# ZB-RC-8_Remote-v01-001.net
KiCad netlist of a schematic drawn in EAGLE
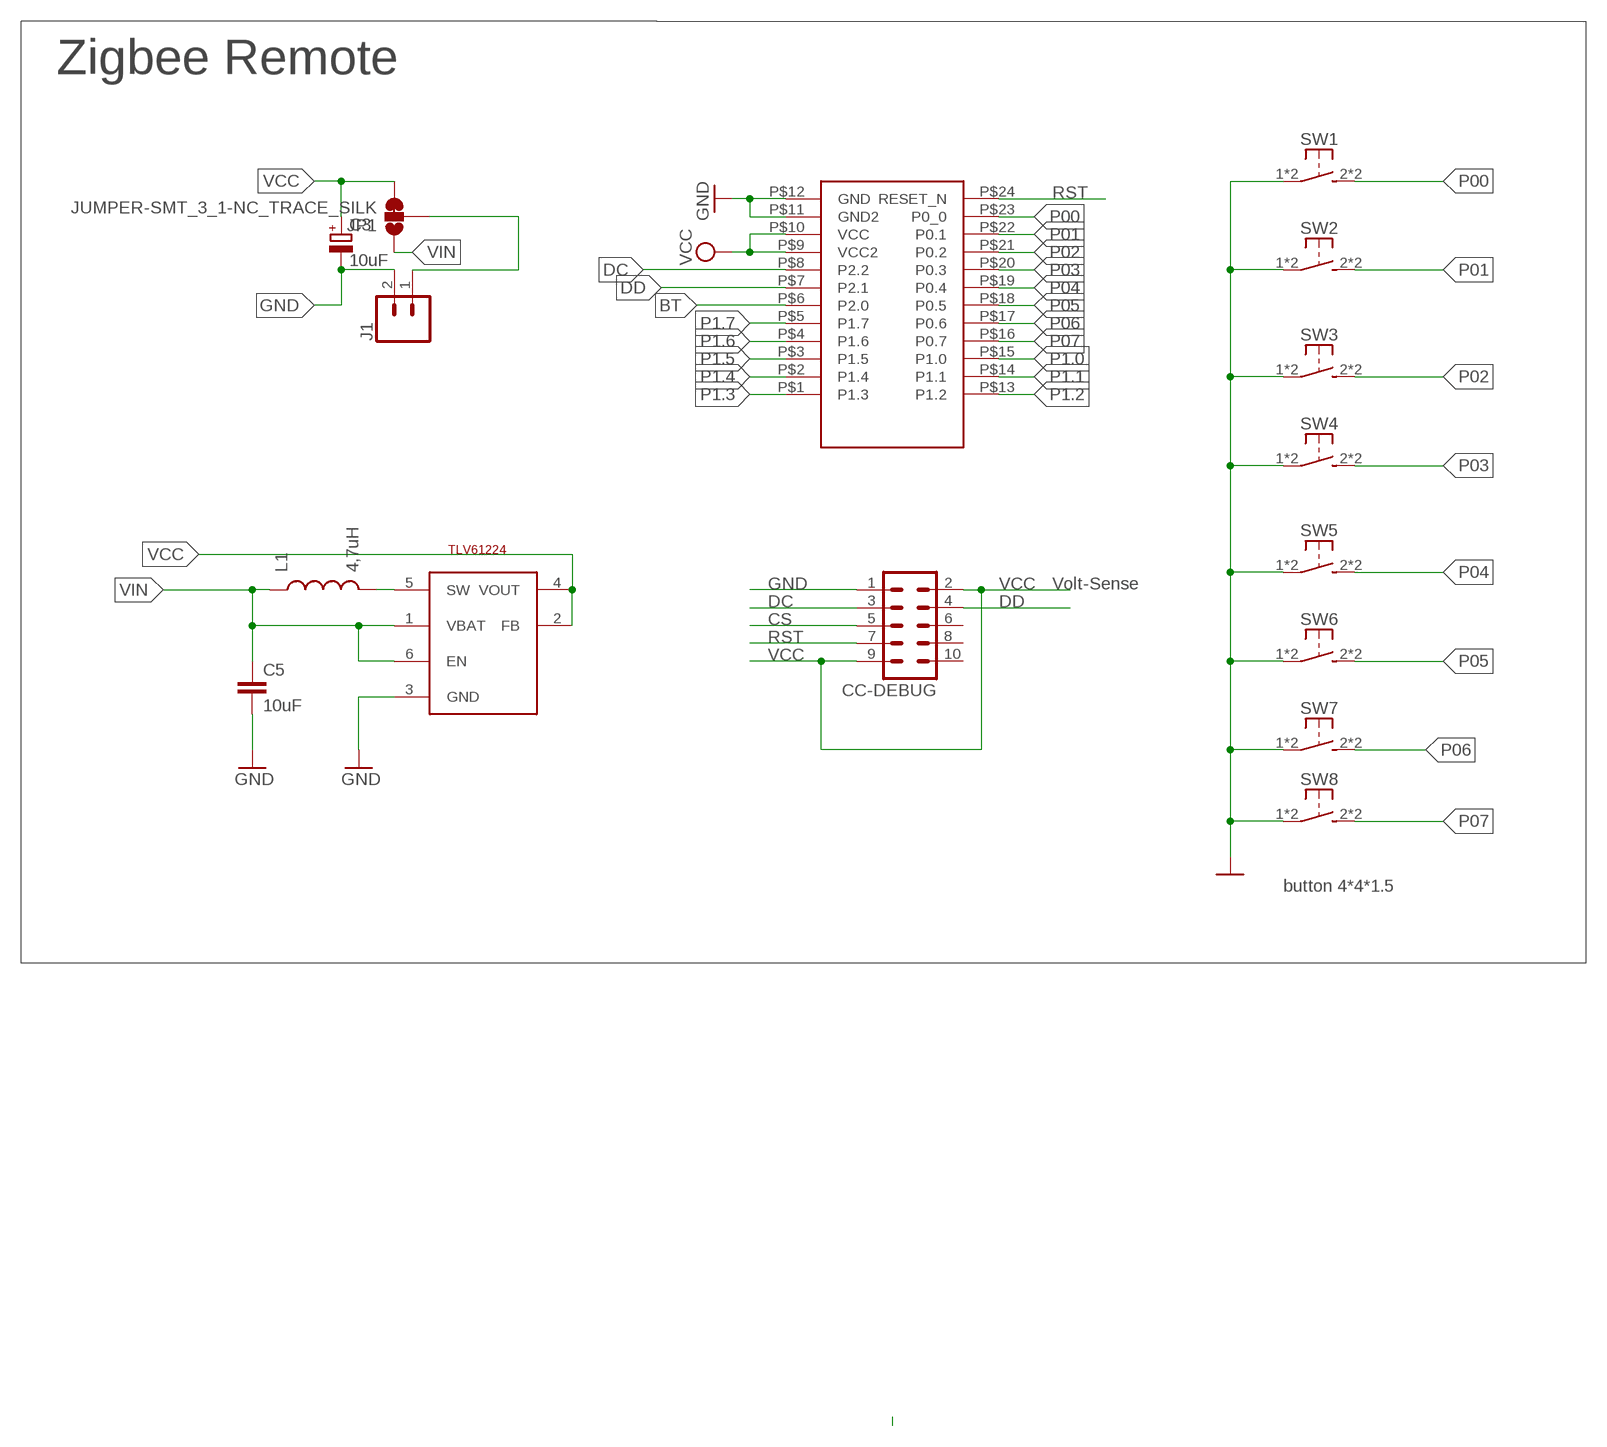
[diagram p0: schematic, sheet 1]

(export (version "E")
  (design (tool "Eeschema 10.0.6"))
  (components
    (comp (ref "C3")
      (value "10uF")
      (footprint "eagle-import:SMC_C")
      (libsource (lib "eagle-import") (part "CPOL-EUSMCC"))
    )
    (comp (ref "C5")
      (value "10uF")
      (footprint "eagle-import:0805")
      (libsource (lib "eagle-import") (part "CAP0805"))
    )
    (comp (ref "CC-DEBUG")
      (value "MA05-2")
      (footprint "eagle-import:MA05-2")
      (libsource (lib "eagle-import") (part "MA05-2"))
    )
    (comp (ref "J1")
      (value "CONN_02PTH3")
      (footprint "eagle-import:1X02_LONGPADS")
      (libsource (lib "eagle-import") (part "CONN_02PTH3"))
    )
    (comp (ref "JP1")
      (value "JUMPER-SMT_3_1-NC_TRACE_SILK")
      (footprint "eagle-import:SMT-JUMPER_3_1-NC_TRACE_SILK")
      (libsource (lib "eagle-import") (part "JUMPER-SMT_3_1-NC_TRACE_SILK"))
    )
    (comp (ref "L1")
      (value "4,7uH")
      (footprint "eagle-import:0805")
      (libsource (lib "eagle-import") (part "INDUCTOR0805"))
    )
    (comp (ref "STEPUP")
      (value "TLV61224")
      (footprint "eagle-import:SOT23-6L")
      (libsource (lib "eagle-import") (part "TI-TLV61224"))
    )
    (comp (ref "SW1")
      (value "SW-TACTILE-TL3305")
      (footprint "eagle-import:TL3305")
      (libsource (lib "eagle-import") (part "SW-TACTILE-TL3305"))
    )
    (comp (ref "SW2")
      (value "SW-TACTILE-TL3305")
      (footprint "eagle-import:TL3305")
      (libsource (lib "eagle-import") (part "SW-TACTILE-TL3305"))
    )
    (comp (ref "SW3")
      (value "SW-TACTILE-TL3305")
      (footprint "eagle-import:TL3305")
      (libsource (lib "eagle-import") (part "SW-TACTILE-TL3305"))
    )
    (comp (ref "SW4")
      (value "SW-TACTILE-TL3305")
      (footprint "eagle-import:TL3305")
      (libsource (lib "eagle-import") (part "SW-TACTILE-TL3305"))
    )
    (comp (ref "SW5")
      (value "SW-TACTILE-TL3305")
      (footprint "eagle-import:TL3305")
      (libsource (lib "eagle-import") (part "SW-TACTILE-TL3305"))
    )
    (comp (ref "SW6")
      (value "SW-TACTILE-TL3305")
      (footprint "eagle-import:TL3305")
      (libsource (lib "eagle-import") (part "SW-TACTILE-TL3305"))
    )
    (comp (ref "SW7")
      (value "SW-TACTILE-TL3305")
      (footprint "eagle-import:TL3305")
      (libsource (lib "eagle-import") (part "SW-TACTILE-TL3305"))
    )
    (comp (ref "SW8")
      (value "SW-TACTILE-TL3305")
      (footprint "eagle-import:TL3305")
      (libsource (lib "eagle-import") (part "SW-TACTILE-TL3305"))
    )
    (comp (ref "U$1")
      (value "CC2530")
      (footprint "eagle-import:SZ1ZIGBEE-SMD")
      (libsource (lib "eagle-import") (part "CC2530"))
    )
  )
  (nets
    (net (code "1") (name "/CS") (class "Default")
      (node (ref "CC-DEBUG") (pin "5") (pinfunction "5_5") (pintype "passive"))
    )
    (net (code "2") (name "/RST") (class "Default")
      (node (ref "CC-DEBUG") (pin "7") (pinfunction "7_7") (pintype "passive"))
      (node (ref "U$1") (pin "P$24") (pinfunction "RESET_N_P$24") (pintype "bidirectional"))
    )
    (net (code "3") (name "BT") (class "Default")
      (node (ref "U$1") (pin "P$6") (pinfunction "P2.0_P$6") (pintype "bidirectional"))
    )
    (net (code "4") (name "DC") (class "Default")
      (node (ref "CC-DEBUG") (pin "3") (pinfunction "3_3") (pintype "passive"))
      (node (ref "U$1") (pin "P$8") (pinfunction "P2.2_P$8") (pintype "bidirectional"))
    )
    (net (code "5") (name "DD") (class "Default")
      (node (ref "CC-DEBUG") (pin "4") (pinfunction "4_4") (pintype "passive"))
      (node (ref "U$1") (pin "P$7") (pinfunction "P2.1_P$7") (pintype "bidirectional"))
    )
    (net (code "6") (name "GND") (class "Default")
      (node (ref "C3") (pin "-") (pinfunction "-_-") (pintype "passive"))
      (node (ref "C5") (pin "2") (pinfunction "2_2") (pintype "passive"))
      (node (ref "CC-DEBUG") (pin "1") (pinfunction "1_1") (pintype "passive"))
      (node (ref "J1") (pin "2") (pinfunction "2_2") (pintype "passive"))
      (node (ref "STEPUP") (pin "3") (pinfunction "GND_3") (pintype "power_in"))
      (node (ref "SW1") (pin "1") (pinfunction "P1_1") (pintype "passive"))
      (node (ref "SW1") (pin "4") (pinfunction "P1_4") (pintype "passive"))
      (node (ref "SW2") (pin "1") (pinfunction "P1_1") (pintype "passive"))
      (node (ref "SW2") (pin "4") (pinfunction "P1_4") (pintype "passive"))
      (node (ref "SW3") (pin "1") (pinfunction "P1_1") (pintype "passive"))
      (node (ref "SW3") (pin "4") (pinfunction "P1_4") (pintype "passive"))
      (node (ref "SW4") (pin "1") (pinfunction "P1_1") (pintype "passive"))
      (node (ref "SW4") (pin "4") (pinfunction "P1_4") (pintype "passive"))
      (node (ref "SW5") (pin "1") (pinfunction "P1_1") (pintype "passive"))
      (node (ref "SW5") (pin "4") (pinfunction "P1_4") (pintype "passive"))
      (node (ref "SW6") (pin "1") (pinfunction "P1_1") (pintype "passive"))
      (node (ref "SW6") (pin "4") (pinfunction "P1_4") (pintype "passive"))
      (node (ref "SW7") (pin "1") (pinfunction "P1_1") (pintype "passive"))
      (node (ref "SW7") (pin "4") (pinfunction "P1_4") (pintype "passive"))
      (node (ref "SW8") (pin "1") (pinfunction "P1_1") (pintype "passive"))
      (node (ref "SW8") (pin "4") (pinfunction "P1_4") (pintype "passive"))
      (node (ref "U$1") (pin "P$11") (pinfunction "GND2_P$11") (pintype "bidirectional"))
      (node (ref "U$1") (pin "P$12") (pinfunction "GND_P$12") (pintype "bidirectional"))
    )
    (net (code "7") (name "Net-(J1-Pad1)") (class "Default")
      (node (ref "J1") (pin "1") (pinfunction "1_1") (pintype "passive"))
      (node (ref "JP1") (pin "2") (pinfunction "2_2") (pintype "passive"))
    )
    (net (code "8") (name "Net-(STEPUP-SW)") (class "Default")
      (node (ref "L1") (pin "2") (pinfunction "2_2") (pintype "passive"))
      (node (ref "STEPUP") (pin "5") (pinfunction "SW_5") (pintype "power_in"))
    )
    (net (code "9") (name "P00") (class "Default")
      (node (ref "SW1") (pin "2") (pinfunction "S1_2") (pintype "passive"))
      (node (ref "SW1") (pin "3") (pinfunction "S1_3") (pintype "passive"))
      (node (ref "U$1") (pin "P$23") (pinfunction "P0_0_P$23") (pintype "bidirectional"))
    )
    (net (code "10") (name "P01") (class "Default")
      (node (ref "SW2") (pin "2") (pinfunction "S1_2") (pintype "passive"))
      (node (ref "SW2") (pin "3") (pinfunction "S1_3") (pintype "passive"))
      (node (ref "U$1") (pin "P$22") (pinfunction "P0.1_P$22") (pintype "bidirectional"))
    )
    (net (code "11") (name "P1.0") (class "Default")
      (node (ref "U$1") (pin "P$15") (pinfunction "P1.0_P$15") (pintype "bidirectional"))
    )
    (net (code "12") (name "P1.1") (class "Default")
      (node (ref "U$1") (pin "P$14") (pinfunction "P1.1_P$14") (pintype "bidirectional"))
    )
    (net (code "13") (name "P1.2") (class "Default")
      (node (ref "U$1") (pin "P$13") (pinfunction "P1.2_P$13") (pintype "bidirectional"))
    )
    (net (code "14") (name "P1.3") (class "Default")
      (node (ref "U$1") (pin "P$1") (pinfunction "P1.3_P$1") (pintype "bidirectional"))
    )
    (net (code "15") (name "P1.4") (class "Default")
      (node (ref "U$1") (pin "P$2") (pinfunction "P1.4_P$2") (pintype "bidirectional"))
    )
    (net (code "16") (name "P1.5") (class "Default")
      (node (ref "U$1") (pin "P$3") (pinfunction "P1.5_P$3") (pintype "bidirectional"))
    )
    (net (code "17") (name "P1.6") (class "Default")
      (node (ref "U$1") (pin "P$4") (pinfunction "P1.6_P$4") (pintype "bidirectional"))
    )
    (net (code "18") (name "P1.7") (class "Default")
      (node (ref "U$1") (pin "P$5") (pinfunction "P1.7_P$5") (pintype "bidirectional"))
    )
    (net (code "19") (name "P02") (class "Default")
      (node (ref "SW3") (pin "2") (pinfunction "S1_2") (pintype "passive"))
      (node (ref "SW3") (pin "3") (pinfunction "S1_3") (pintype "passive"))
      (node (ref "U$1") (pin "P$21") (pinfunction "P0.2_P$21") (pintype "bidirectional"))
    )
    (net (code "20") (name "P03") (class "Default")
      (node (ref "SW4") (pin "2") (pinfunction "S1_2") (pintype "passive"))
      (node (ref "SW4") (pin "3") (pinfunction "S1_3") (pintype "passive"))
      (node (ref "U$1") (pin "P$20") (pinfunction "P0.3_P$20") (pintype "bidirectional"))
    )
    (net (code "21") (name "P04") (class "Default")
      (node (ref "SW5") (pin "2") (pinfunction "S1_2") (pintype "passive"))
      (node (ref "SW5") (pin "3") (pinfunction "S1_3") (pintype "passive"))
      (node (ref "U$1") (pin "P$19") (pinfunction "P0.4_P$19") (pintype "bidirectional"))
    )
    (net (code "22") (name "P05") (class "Default")
      (node (ref "SW6") (pin "2") (pinfunction "S1_2") (pintype "passive"))
      (node (ref "SW6") (pin "3") (pinfunction "S1_3") (pintype "passive"))
      (node (ref "U$1") (pin "P$18") (pinfunction "P0.5_P$18") (pintype "bidirectional"))
    )
    (net (code "23") (name "P06") (class "Default")
      (node (ref "SW7") (pin "2") (pinfunction "S1_2") (pintype "passive"))
      (node (ref "SW7") (pin "3") (pinfunction "S1_3") (pintype "passive"))
      (node (ref "U$1") (pin "P$17") (pinfunction "P0.6_P$17") (pintype "bidirectional"))
    )
    (net (code "24") (name "P07") (class "Default")
      (node (ref "SW8") (pin "2") (pinfunction "S1_2") (pintype "passive"))
      (node (ref "SW8") (pin "3") (pinfunction "S1_3") (pintype "passive"))
      (node (ref "U$1") (pin "P$16") (pinfunction "P0.7_P$16") (pintype "bidirectional"))
    )
    (net (code "25") (name "VCC") (class "Default")
      (node (ref "C3") (pin "+") (pinfunction "+_+") (pintype "passive"))
      (node (ref "CC-DEBUG") (pin "2") (pinfunction "2_2") (pintype "passive"))
      (node (ref "CC-DEBUG") (pin "9") (pinfunction "9_9") (pintype "passive"))
      (node (ref "JP1") (pin "3") (pinfunction "3_3") (pintype "passive"))
      (node (ref "STEPUP") (pin "2") (pinfunction "FB_2") (pintype "input"))
      (node (ref "STEPUP") (pin "4") (pinfunction "VOUT_4") (pintype "power_in"))
      (node (ref "U$1") (pin "P$10") (pinfunction "VCC_P$10") (pintype "bidirectional"))
      (node (ref "U$1") (pin "P$9") (pinfunction "VCC2_P$9") (pintype "bidirectional"))
    )
    (net (code "26") (name "VIN") (class "Default")
      (node (ref "C5") (pin "1") (pinfunction "1_1") (pintype "passive"))
      (node (ref "JP1") (pin "1") (pinfunction "1_1") (pintype "passive"))
      (node (ref "L1") (pin "1") (pinfunction "1_1") (pintype "passive"))
      (node (ref "STEPUP") (pin "1") (pinfunction "VBAT_1") (pintype "power_in"))
      (node (ref "STEPUP") (pin "6") (pinfunction "EN_6") (pintype "input"))
    )
    (net (code "27") (name "unconnected-(CC-DEBUG-Pad6)") (class "Default")
      (node (ref "CC-DEBUG") (pin "6") (pinfunction "6_6") (pintype "passive"))
    )
    (net (code "28") (name "unconnected-(CC-DEBUG-Pad8)") (class "Default")
      (node (ref "CC-DEBUG") (pin "8") (pinfunction "8_8") (pintype "passive"))
    )
    (net (code "29") (name "unconnected-(CC-DEBUG-Pad10)") (class "Default")
      (node (ref "CC-DEBUG") (pin "10") (pinfunction "10_10") (pintype "passive"))
    )
  )
)
